# Copy_of_ADC_schematic_Brad.net
KiCad netlist of a schematic drawn in Altium Designer
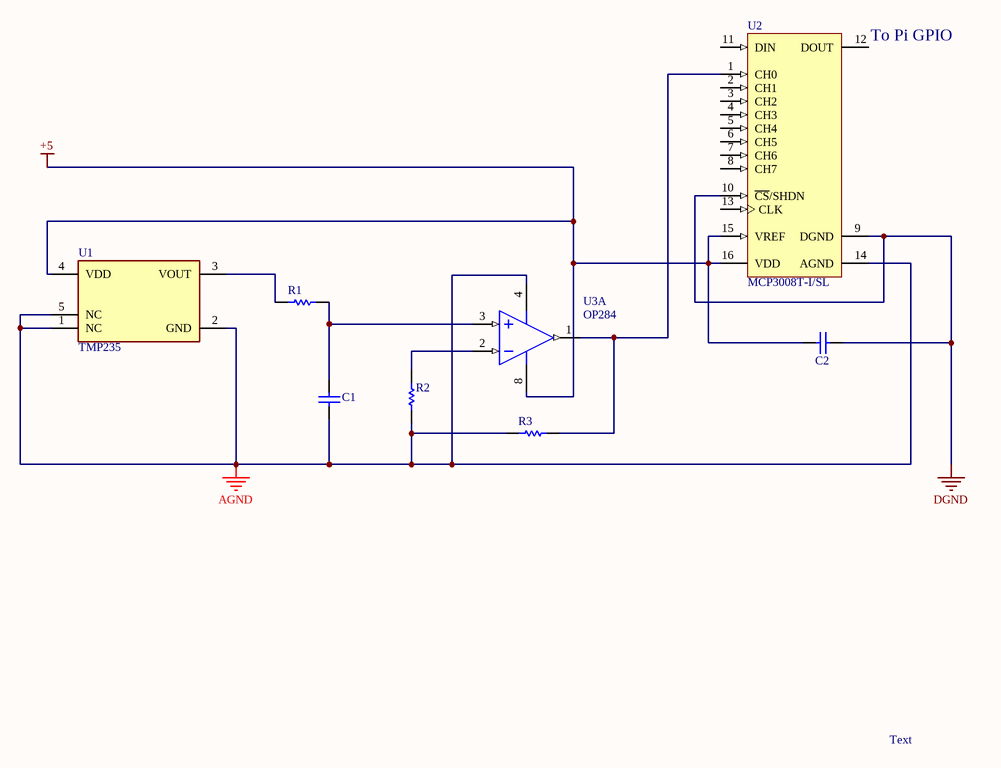
[diagram p0: Copy of ADC_schematic_Brad.SchDoc]

(export (version "E")
  (design (tool "Eeschema 10.0.6"))
  (components
    (comp (ref "C1")
      (value "~")
      (footprint "CAPC3216X180X50ML20T25")
      (fields (field (name "TOLERANCE") "1%"))
      (libsource (lib "Altium Content Vault") (part "CAP-NP-2"))
    )
    (comp (ref "C2")
      (value "1 uF, 50V 1206(3216)")
      (footprint "CAPC3216X125X55LL15T25")
      (description "Chip Capacitor, 1 uF, +/- 10%, 50 V, -55 to 125 degC, 1206 (3216 Metric), RoHS, Tape and Reel")
      (fields (field (name "TOLERANCE") "10%") (field (name "MANUFACTURER") "Murata"))
      (libsource (lib "Altium Content Vault") (part "CAP-NP-2"))
    )
    (comp (ref "R1")
      (value "10K 2010(5025)")
      (footprint "RESC2010(5025)_L")
      (description "10K 0.75W 5% 2010 (5025 Metric)  SMD")
      (fields (field (name "TOLERANCE") "5 %") (field (name "POWER") "0.75 W"))
      (libsource (lib "Altium Content Vault") (part "RES"))
    )
    (comp (ref "R2")
      (value "10K 2010(5025)")
      (footprint "RESC2010(5025)_L")
      (description "10K 0.75W 5% 2010 (5025 Metric)  SMD")
      (fields (field (name "TOLERANCE") "5 %") (field (name "POWER") "0.75 W"))
      (libsource (lib "Altium Content Vault") (part "RES"))
    )
    (comp (ref "R3")
      (value "6K8 2010(5025)")
      (footprint "RESC2010(5025)_N")
      (description "6K8 0.75W 1% 2010 (5025 Metric)  SMD")
      (fields (field (name "POWER") "0.75 W") (field (name "TOLERANCE") "1 %"))
      (libsource (lib "Altium Content Vault") (part "RES"))
    )
    (comp (ref "U1")
      (value "TMP235")
      (footprint "FP-DCK0005A-MFG")
      (description "SENSOR ANALOG -40C-150C SC70-5")
      (fields
        (field (name "MANUFACTURER PART NUMBER") "TMP235A4DCKR")
        (field (name "MANUFACTURER") "Texas Instruments")
      )
      (libsource (lib "Altium Content Vault") (part "95db8c7ceedc91514cec36ab6d7b9b1"))
    )
    (comp (ref "U2")
      (value "MCP3008T-I/SL")
      (footprint "SOIC-SL16_N")
      (libsource (lib "Altium Content Vault") (part "CON-ADC-MCP3008-16"))
    )
    (comp (ref "U3")
      (value "OP284")
      (footprint "ADI-R-8_N")
      (fields (field (name "PARTNUMBER") "OP284FSZ") (field (name "MANUFACTURER") "Analog Devices"))
      (libsource (lib "Altium Content Vault") (part "ADI-OP29X-R-8"))
    )
  )
  (nets
    (net (code "1") (name "+5") (class "Default")
      (node (ref "C2") (pin "1") (pinfunction "1_1") (pintype "passive"))
      (node (ref "U1") (pin "4") (pinfunction "VDD_4") (pintype "power_in"))
      (node (ref "U2") (pin "15") (pinfunction "VREF_15") (pintype "input"))
      (node (ref "U2") (pin "16") (pinfunction "VDD_16") (pintype "power_in"))
      (node (ref "U3") (pin "8") (pinfunction "+V_8") (pintype "power_in"))
    )
    (net (code "2") (name "AGND") (class "Default")
      (node (ref "C1") (pin "1") (pinfunction "1_1") (pintype "passive"))
      (node (ref "R2") (pin "1") (pinfunction "1_1") (pintype "passive"))
      (node (ref "R3") (pin "1") (pinfunction "1_1") (pintype "passive"))
      (node (ref "U1") (pin "1") (pinfunction "NC_1") (pintype "passive"))
      (node (ref "U1") (pin "2") (pinfunction "GND_2") (pintype "power_in"))
      (node (ref "U1") (pin "5") (pinfunction "NC_5") (pintype "passive"))
      (node (ref "U2") (pin "14") (pinfunction "AGND_14") (pintype "power_in"))
      (node (ref "U3") (pin "4") (pinfunction "-V_4") (pintype "power_in"))
    )
    (net (code "3") (name "DGND") (class "Default")
      (node (ref "C2") (pin "2") (pinfunction "2_2") (pintype "passive"))
      (node (ref "U2") (pin "10") (pinfunction "~{CS}/SHDN_10") (pintype "input"))
      (node (ref "U2") (pin "9") (pinfunction "DGND_9") (pintype "power_in"))
    )
    (net (code "4") (name "Net-(U1-VOUT)") (class "Default")
      (node (ref "R1") (pin "1") (pinfunction "1_1") (pintype "passive"))
      (node (ref "U1") (pin "3") (pinfunction "VOUT_3") (pintype "passive"))
    )
    (net (code "5") (name "Net-(U2-CH0)") (class "Default")
      (node (ref "R3") (pin "2") (pinfunction "2_2") (pintype "passive"))
      (node (ref "U2") (pin "1") (pinfunction "CH0_1") (pintype "input"))
      (node (ref "U3") (pin "1") (pinfunction "OUT_A_1") (pintype "output"))
    )
    (net (code "6") (name "Net-(U3A-+IN_A)") (class "Default")
      (node (ref "C1") (pin "2") (pinfunction "2_2") (pintype "passive"))
      (node (ref "R1") (pin "2") (pinfunction "2_2") (pintype "passive"))
      (node (ref "U3") (pin "3") (pinfunction "+IN_A_3") (pintype "input"))
    )
    (net (code "7") (name "Net-(U3A--IN_A)") (class "Default")
      (node (ref "R2") (pin "2") (pinfunction "2_2") (pintype "passive"))
      (node (ref "U3") (pin "2") (pinfunction "-IN_A_2") (pintype "input"))
    )
    (net (code "8") (name "unconnected-(U2-CH1-Pad2)") (class "Default")
      (node (ref "U2") (pin "2") (pinfunction "CH1_2") (pintype "input"))
    )
    (net (code "9") (name "unconnected-(U2-CH2-Pad3)") (class "Default")
      (node (ref "U2") (pin "3") (pinfunction "CH2_3") (pintype "input"))
    )
    (net (code "10") (name "unconnected-(U2-CH3-Pad4)") (class "Default")
      (node (ref "U2") (pin "4") (pinfunction "CH3_4") (pintype "input"))
    )
    (net (code "11") (name "unconnected-(U2-CH4-Pad5)") (class "Default")
      (node (ref "U2") (pin "5") (pinfunction "CH4_5") (pintype "input"))
    )
    (net (code "12") (name "unconnected-(U2-CH5-Pad6)") (class "Default")
      (node (ref "U2") (pin "6") (pinfunction "CH5_6") (pintype "input"))
    )
    (net (code "13") (name "unconnected-(U2-CH6-Pad7)") (class "Default")
      (node (ref "U2") (pin "7") (pinfunction "CH6_7") (pintype "input"))
    )
    (net (code "14") (name "unconnected-(U2-CH7-Pad8)") (class "Default")
      (node (ref "U2") (pin "8") (pinfunction "CH7_8") (pintype "input"))
    )
    (net (code "15") (name "unconnected-(U2-CLK-Pad13)") (class "Default")
      (node (ref "U2") (pin "13") (pinfunction "CLK_13") (pintype "input"))
    )
    (net (code "16") (name "unconnected-(U2-DIN-Pad11)") (class "Default")
      (node (ref "U2") (pin "11") (pinfunction "DIN_11") (pintype "input"))
    )
    (net (code "17") (name "unconnected-(U2-DOUT-Pad12)") (class "Default")
      (node (ref "U2") (pin "12") (pinfunction "DOUT_12") (pintype "tri_state"))
    )
  )
)
